# In.net
KiCad netlist of a schematic drawn in Altium Designer
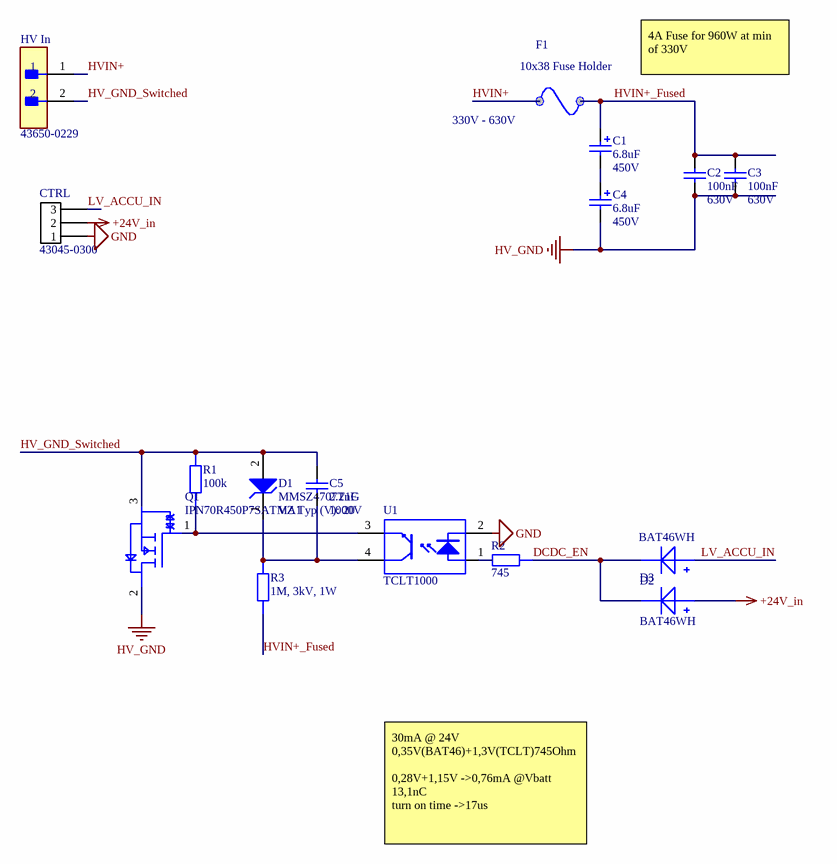
[diagram p0: In.SchDoc]

(export (version "E")
  (design (tool "Eeschema 10.0.6"))
  (components
    (comp (ref "C1")
      (value "6.8uF")
      (footprint "WCAP-AT1H_D13H20")
      (description "WCAP-AT1H Aluminum Electrolytic Capacitor, Radial, THT, D13xH20mm, 6.8uF, 450V")
      (fields
        (field (name "MANUFACTURER PART NUMBER") "860241478002")
        (field (name "MANUFACTURER") "Wurth Elektronik")
        (field (name "VOLTAGE") "450V")
      )
      (libsource (lib "Altium_WCAP-AT1H (rev20b)") (part "860241478002"))
    )
    (comp (ref "C2")
      (value "~")
      (footprint "WCAP-CSMH_1812_H2")
      (description "WCAP-CSMH Multilayer Ceramic Chip Capacitor, size 1812, X7R Class II, 100nF, 630V")
      (fields
        (field (name "MANUFACTURER PART NUMBER") "885342211006")
        (field (name "CAPACITANCE") "100nF")
        (field (name "MANUFACTURER") "Wurth Elektronik")
        (field (name "VOLTAGE") "630V")
      )
      (libsource (lib "Altium_WCAP-CSMH (rev20a)") (part "885342211006"))
    )
    (comp (ref "C3")
      (value "~")
      (footprint "WCAP-CSMH_1812_H2")
      (description "WCAP-CSMH Multilayer Ceramic Chip Capacitor, size 1812, X7R Class II, 100nF, 630V")
      (fields
        (field (name "MANUFACTURER PART NUMBER") "885342211006")
        (field (name "CAPACITANCE") "100nF")
        (field (name "MANUFACTURER") "Wurth Elektronik")
        (field (name "VOLTAGE") "630V")
      )
      (libsource (lib "Altium_WCAP-CSMH (rev20a)") (part "885342211006"))
    )
    (comp (ref "C4")
      (value "6.8uF")
      (footprint "WCAP-AT1H_D13H20")
      (description "WCAP-AT1H Aluminum Electrolytic Capacitor, Radial, THT, D13xH20mm, 6.8uF, 450V")
      (fields
        (field (name "MANUFACTURER PART NUMBER") "860241478002")
        (field (name "MANUFACTURER") "Wurth Elektronik")
        (field (name "VOLTAGE") "450V")
      )
      (libsource (lib "Altium_WCAP-AT1H (rev20b)") (part "860241478002"))
    )
    (comp (ref "C5")
      (value "~")
      (footprint "WCAP-CSMH_0805_H1.25")
      (description "WCAP-CSMH Multilayer Ceramic Chip Capacitor, size 0805, X7R Class II, 2.2nF, 1000V")
      (fields
        (field (name "MANUFACTURER PART NUMBER") "885342207016")
        (field (name "CAPACITANCE") "2.2nF")
        (field (name "MANUFACTURER") "Wurth Elektronik")
        (field (name "VOLTAGE") "1000V")
      )
      (libsource (lib "Altium_WCAP-CSMH (rev20a)") (part "885342207016"))
    )
    (comp (ref "CTRL")
      (value "43045-0300")
      (footprint "43650-0315")
      (description "Molex Micro-Fit 3.0 3-Pin\r\n600V\r\n8.5A")
      (libsource (lib "Standardbauteile") (part "MicroFit3.0 3-Pin"))
    )
    (comp (ref "D1")
      (value "MMSZ4707T1G")
      (footprint "ONSC-SOD-123-2-425-04_V")
      (description "Zener Voltage Regulator, 500 mW, 2-Pin SOD-123, Pb-Free, Tape and Reel")
      (fields (field (name "MANUFACTURER") "On Semiconductor") (field (name "VZ TYP (V)") "20"))
      (libsource (lib "Altium Content Vault") (part "ONSC-K1A2-2"))
    )
    (comp (ref "D2")
      (value "BAT46WH")
      (footprint "DIOM2715X18N")
      (libsource (lib "Integrated_LibraryLukas_New") (part "BAT46WH"))
    )
    (comp (ref "D3")
      (value "BAT46WH")
      (footprint "DIOM2715X18N")
      (libsource (lib "Integrated_LibraryLukas_New") (part "BAT46WH"))
    )
    (comp (ref "F1")
      (value "10x38 Fuse Holder")
      (footprint "10x38 Fuse")
      (libsource (lib "Integrated_LibraryLukas_New") (part "10x38 Fuse Holder"))
    )
    (comp (ref "HV In")
      (value "43650-0229")
      (footprint "FP-43650-0229-MFG")
      (description "CONN HEADER VERT 2POS 3MM")
      (fields
        (field (name "OCTOPART") "https://octopart.com/43650-0229-molex-7652326")
        (field (name "MANUFACTURER") "Molex")
      )
      (libsource (lib "Altium Content Vault") (part "3bc925449376181038e59eaffc5286c"))
    )
    (comp (ref "Q1")
      (value "IPN70R450P7SATMA1")
      (footprint "SOT230P700X180-4L")
      (description "IPN70R450P7S Series 700 V 10 A 7.1 W CoolMOS P7 Power Transistor - PG-SOT-223")
      (fields (field (name "MANUFACTURER") "Infineon"))
      (libsource (lib "Integrated_LibraryLukas_New") (part "IPN70R450P7SATMA1"))
    )
    (comp (ref "R1")
      (value "100k")
      (footprint "STACKPOLE CSR0603")
      (description "Resistor with multiple footprints")
      (fields (field (name "Comment") "SMD Resistor"))
      (libsource (lib "Standardbauteile") (part "SMD Resistor"))
    )
    (comp (ref "R2")
      (value "745")
      (footprint "STACKPOLE CSR0603")
      (description "Resistor with multiple footprints")
      (fields (field (name "Comment") "SMD Resistor"))
      (libsource (lib "Standardbauteile") (part "SMD Resistor"))
    )
    (comp (ref "R3")
      (value "1M, 3kV, 1W")
      (footprint "STACKPOLE CSRN2512")
      (description "Resistor with multiple footprints")
      (fields (field (name "Comment") "CHV2512-FX-1004ELF"))
      (libsource (lib "Standardbauteile") (part "SMD Resistor"))
    )
    (comp (ref "U1")
      (value "TCLT1000")
      (footprint "VISH-SOP4L-4_V")
      (fields (field (name "MANUFACTURER") "Vishay/Semiconductor"))
      (libsource (lib "Altium Content Vault") (part "OPTO-ACEC-4"))
    )
  )
  (nets
    (net (code "1") (name "+24V_in") (class "Default")
      (node (ref "CTRL") (pin "2") (pinfunction "2_2") (pintype "passive"))
      (node (ref "D3") (pin "1") (pintype "passive"))
    )
    (net (code "2") (name "/DCDC_EN") (class "Default")
      (node (ref "D2") (pin "2") (pintype "passive"))
      (node (ref "D3") (pin "2") (pintype "passive"))
      (node (ref "R2") (pin "2") (pinfunction "2_2") (pintype "passive"))
    )
    (net (code "3") (name "/HVIN+") (class "Default")
      (node (ref "F1") (pin "2") (pintype "passive"))
      (node (ref "HV In") (pin "1") (pinfunction "1_1") (pintype "passive"))
    )
    (net (code "4") (name "/HVIN+_Fused") (class "Default")
      (node (ref "C1") (pin "1") (pinfunction "P_1") (pintype "passive"))
      (node (ref "C2") (pin "1") (pinfunction "1_1") (pintype "passive"))
      (node (ref "C3") (pin "1") (pinfunction "1_1") (pintype "passive"))
      (node (ref "F1") (pin "1") (pintype "passive"))
      (node (ref "R3") (pin "2") (pinfunction "2_2") (pintype "passive"))
    )
    (net (code "5") (name "/HV_GND_Switched") (class "Default")
      (node (ref "C5") (pin "2") (pinfunction "2_2") (pintype "passive"))
      (node (ref "D1") (pin "2") (pinfunction "A_2") (pintype "passive"))
      (node (ref "HV In") (pin "2") (pinfunction "2_2") (pintype "passive"))
      (node (ref "Q1") (pin "3") (pintype "passive"))
      (node (ref "R1") (pin "1") (pinfunction "1_1") (pintype "passive"))
    )
    (net (code "6") (name "/LV_ACCU_IN") (class "Default")
      (node (ref "CTRL") (pin "3") (pinfunction "3_3") (pintype "passive"))
      (node (ref "D2") (pin "1") (pintype "passive"))
    )
    (net (code "7") (name "GND") (class "Default")
      (node (ref "CTRL") (pin "1") (pinfunction "1_1") (pintype "passive"))
      (node (ref "U1") (pin "2") (pinfunction "C_2") (pintype "passive"))
    )
    (net (code "8") (name "HV_GND") (class "Default")
      (node (ref "C2") (pin "2") (pinfunction "2_2") (pintype "passive"))
      (node (ref "C3") (pin "2") (pinfunction "2_2") (pintype "passive"))
      (node (ref "C4") (pin "2") (pinfunction "N_2") (pintype "passive"))
      (node (ref "Q1") (pin "2") (pintype "passive"))
    )
    (net (code "9") (name "Net-(C1-N)") (class "Default")
      (node (ref "C1") (pin "2") (pinfunction "N_2") (pintype "passive"))
      (node (ref "C4") (pin "1") (pinfunction "P_1") (pintype "passive"))
    )
    (net (code "10") (name "Net-(D1-K)") (class "Default")
      (node (ref "C5") (pin "1") (pinfunction "1_1") (pintype "passive"))
      (node (ref "D1") (pin "1") (pinfunction "K_1") (pintype "passive"))
      (node (ref "R3") (pin "1") (pinfunction "1_1") (pintype "passive"))
      (node (ref "U1") (pin "4") (pinfunction "C_4") (pintype "passive"))
    )
    (net (code "11") (name "Net-(U1-A)") (class "Default")
      (node (ref "R2") (pin "1") (pinfunction "1_1") (pintype "passive"))
      (node (ref "U1") (pin "1") (pinfunction "A_1") (pintype "passive"))
    )
    (net (code "12") (name "Net-(U1-E)") (class "Default")
      (node (ref "Q1") (pin "1") (pintype "passive"))
      (node (ref "R1") (pin "2") (pinfunction "2_2") (pintype "passive"))
      (node (ref "U1") (pin "3") (pinfunction "E_3") (pintype "passive"))
    )
  )
)
